# USBPD_CH211.net
KiCad netlist of a schematic drawn in Altium Designer
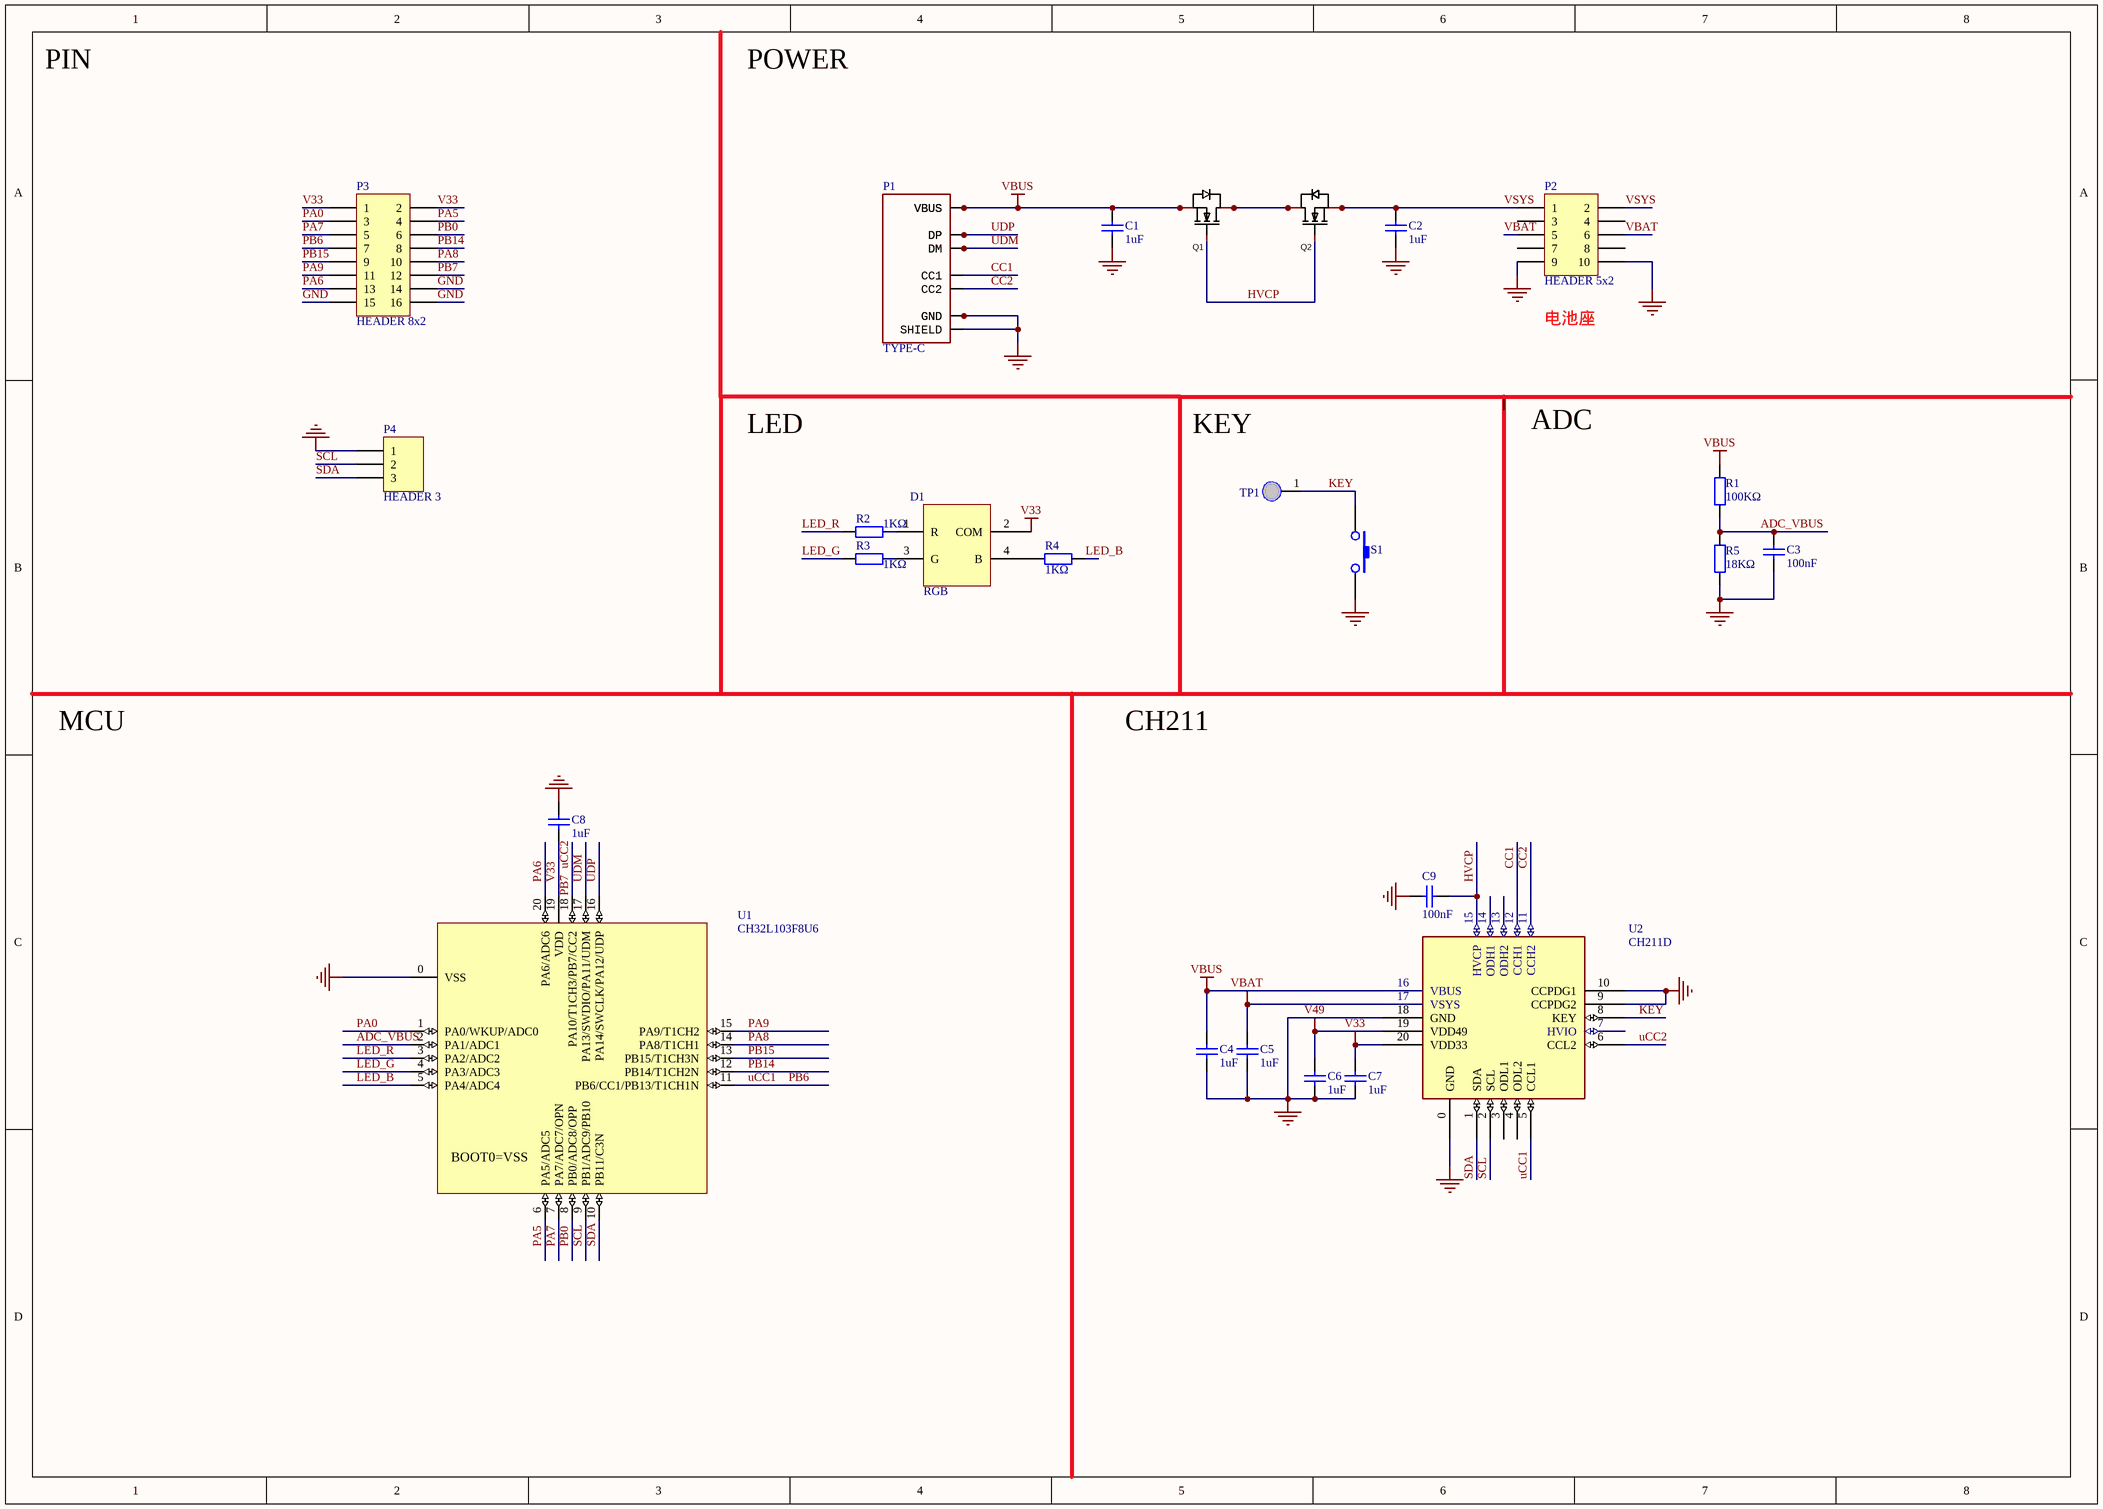
[diagram p0: USBPD_CH211.SchDoc]

(export (version "E")
  (design (tool "Eeschema 10.0.6"))
  (components
    (comp (ref "C1")
      (value "1uF")
      (footprint "0402_C")
      (description "贴片电容")
      (libsource (lib "Miscellaneous Devices LC") (part "0603 100nF (104) 10% 50V"))
    )
    (comp (ref "C2")
      (value "1uF")
      (footprint "0402_C")
      (description "贴片电容")
      (libsource (lib "Miscellaneous Devices LC") (part "0603 100nF (104) 10% 50V"))
    )
    (comp (ref "C3")
      (value "100nF")
      (footprint "0402_C")
      (description "贴片电容")
      (libsource (lib "Miscellaneous Devices LC") (part "0603 100nF (104) 10% 50V"))
    )
    (comp (ref "C4")
      (value "1uF")
      (footprint "0402_C")
      (description "贴片电容")
      (libsource (lib "Miscellaneous Devices LC") (part "0603 100nF (104) 10% 50V"))
    )
    (comp (ref "C5")
      (value "1uF")
      (footprint "0402_C")
      (description "贴片电容")
      (libsource (lib "Miscellaneous Devices LC") (part "0603 100nF (104) 10% 50V"))
    )
    (comp (ref "C6")
      (value "1uF")
      (footprint "0402_C")
      (description "贴片电容")
      (libsource (lib "Miscellaneous Devices LC") (part "0603 100nF (104) 10% 50V"))
    )
    (comp (ref "C7")
      (value "1uF")
      (footprint "0402_C")
      (description "贴片电容")
      (libsource (lib "Miscellaneous Devices LC") (part "0603 100nF (104) 10% 50V"))
    )
    (comp (ref "C8")
      (value "1uF")
      (footprint "0402_C")
      (description "贴片电容")
      (libsource (lib "Miscellaneous Devices LC") (part "0603 1uF (105) 10% 50V"))
    )
    (comp (ref "C9")
      (value "100nF")
      (footprint "0402_C")
      (description "贴片电容")
      (libsource (lib "Miscellaneous Devices LC") (part "0603 100nF (104) 10% 50V"))
    )
    (comp (ref "D1")
      (value "RGB")
      (footprint "RGB")
      (description "共阳")
      (libsource (lib "wch_sch_others") (part "RGB"))
    )
    (comp (ref "P1")
      (value "TYPE-C")
      (footprint "TYPE-C-Receptacle-2.0")
      (libsource (lib "Miscellaneous SCH Lib") (part "TYPE-C-Receptacle-RefDesign"))
    )
    (comp (ref "P2")
      (value "HEADER 5x2")
      (footprint "MYPCB:IDC10-2.54mm")
      (description "Header, 5-Pin, Dual row")
      (libsource (lib "wch_sch_others") (part "HEADER 5x2"))
    )
    (comp (ref "P3")
      (value "HEADER 8x2")
      (footprint "MYPCB:IDC16-2.54mm")
      (description "Header, 8-Pin, Dual row")
      (libsource (lib "wch_sch_others") (part "HEADER 8x2"))
    )
    (comp (ref "P4")
      (value "HEADER 3")
      (footprint "SIP3-2.54MM")
      (description "Header, 3-Pin")
      (libsource (lib "wch_sch_others") (part "HEADER 3"))
    )
    (comp (ref "Q1")
      (value "ASDM40N52E-R")
      (footprint "DFN-8_L3.1-W3.0-P0.65-LS3.3-BL")
      (description "DFN_NMOS")
      (fields (field (name "MANUFACTURER") "Ascend(安森德)"))
      (libsource (lib "Zcc") (part "NMOS_DFN3*3.1"))
    )
    (comp (ref "Q2")
      (value "ASDM40N52E-R")
      (footprint "DFN-8_L3.1-W3.0-P0.65-LS3.3-BL")
      (description "DFN_NMOS")
      (fields (field (name "MANUFACTURER") "Ascend(安森德)"))
      (libsource (lib "Zcc") (part "NMOS_DFN3*3.1"))
    )
    (comp (ref "R1")
      (value "100KΩ")
      (footprint "0402")
      (description "贴片电阻")
      (libsource (lib "Miscellaneous Devices LC") (part "0603 100KΩ (1003) 1%"))
    )
    (comp (ref "R2")
      (value "1KΩ")
      (footprint "0402")
      (description "贴片电阻")
      (libsource (lib "") (part "0603 100KΩ (1003) 1%_1"))
    )
    (comp (ref "R3")
      (value "1KΩ")
      (footprint "0402")
      (description "贴片电阻")
      (libsource (lib "") (part "0603 100KΩ (1003) 1%_1"))
    )
    (comp (ref "R4")
      (value "1KΩ")
      (footprint "0402")
      (description "贴片电阻")
      (libsource (lib "") (part "0603 100KΩ (1003) 1%_1"))
    )
    (comp (ref "R5")
      (value "18KΩ")
      (footprint "0402")
      (description "贴片电阻")
      (libsource (lib "Miscellaneous Devices LC") (part "0603 100KΩ (1003) 1%"))
    )
    (comp (ref "S1")
      (value "KEY")
      (footprint "SMD_6.1x3.65x2.5mm-KEY")
      (libsource (lib "wch_sch_others") (part "KEY1"))
    )
    (comp (ref "TP1")
      (value "Testpoint")
      (footprint "TESTPOINT3")
      (description "测试点")
      (libsource (lib "wch_sch_others") (part "Testpoint"))
    )
    (comp (ref "U1")
      (value "CH32L103F8U6")
      (footprint "QFN20_3X3")
      (description "RISC-V LMD-MCU, 96MHz, USB, Type-C/PD-5K1, CAN, OPA, lower power")
      (libsource (lib "DHXXXSCH111") (part "CH32L103F8U6"))
    )
    (comp (ref "U2")
      (value "CH211D")
      (footprint "QFN20_3X3")
      (description "28V USB PD & Type-C high voltage interface")
      (libsource (lib "CHXXX") (part "CH211D"))
    )
  )
  (nets
    (net (code "1") (name "/ADC_VBUS") (class "Default")
      (node (ref "C3") (pin "2") (pinfunction "2_2") (pintype "passive"))
      (node (ref "R1") (pin "2") (pinfunction "2_2") (pintype "passive"))
      (node (ref "R5") (pin "1") (pinfunction "1_1") (pintype "passive"))
      (node (ref "U1") (pin "2") (pinfunction "PA1/ADC1_2") (pintype "bidirectional"))
    )
    (net (code "2") (name "/CC1") (class "Default")
      (node (ref "P1") (pin "A5") (pinfunction "CC1_A5") (pintype "passive"))
      (node (ref "U2") (pin "12") (pinfunction "CCH1_12") (pintype "bidirectional"))
    )
    (net (code "3") (name "/CC2") (class "Default")
      (node (ref "P1") (pin "B5") (pinfunction "CC2_B5") (pintype "passive"))
      (node (ref "U2") (pin "11") (pinfunction "CCH2_11") (pintype "bidirectional"))
    )
    (net (code "4") (name "/HVCP") (class "Default")
      (node (ref "C9") (pin "1") (pinfunction "1_1") (pintype "passive"))
      (node (ref "Q1") (pin "4") (pinfunction "G_4") (pintype "passive"))
      (node (ref "Q2") (pin "4") (pinfunction "G_4") (pintype "passive"))
      (node (ref "U2") (pin "15") (pinfunction "HVCP_15") (pintype "bidirectional"))
    )
    (net (code "5") (name "/KEY") (class "Default")
      (node (ref "S1") (pin "1") (pinfunction "1_1") (pintype "passive"))
      (node (ref "TP1") (pin "1") (pintype "passive"))
      (node (ref "U2") (pin "8") (pinfunction "KEY_8") (pintype "bidirectional"))
    )
    (net (code "6") (name "/LED_B") (class "Default")
      (node (ref "R4") (pin "2") (pinfunction "2_2") (pintype "passive"))
      (node (ref "U1") (pin "5") (pinfunction "PA4/ADC4_5") (pintype "bidirectional"))
    )
    (net (code "7") (name "/LED_G") (class "Default")
      (node (ref "R3") (pin "1") (pinfunction "1_1") (pintype "passive"))
      (node (ref "U1") (pin "4") (pinfunction "PA3/ADC3_4") (pintype "bidirectional"))
    )
    (net (code "8") (name "/LED_R") (class "Default")
      (node (ref "R2") (pin "1") (pinfunction "1_1") (pintype "passive"))
      (node (ref "U1") (pin "3") (pinfunction "PA2/ADC2_3") (pintype "bidirectional"))
    )
    (net (code "9") (name "/PA0") (class "Default")
      (node (ref "P3") (pin "3") (pinfunction "3_3") (pintype "passive"))
      (node (ref "U1") (pin "1") (pinfunction "PA0/WKUP/ADC0_1") (pintype "bidirectional"))
    )
    (net (code "10") (name "/PA5") (class "Default")
      (node (ref "P3") (pin "4") (pinfunction "4_4") (pintype "passive"))
      (node (ref "U1") (pin "6") (pinfunction "PA5/ADC5_6") (pintype "bidirectional"))
    )
    (net (code "11") (name "/PA6") (class "Default")
      (node (ref "P3") (pin "13") (pinfunction "13_13") (pintype "passive"))
      (node (ref "U1") (pin "20") (pinfunction "PA6/ADC6_20") (pintype "bidirectional"))
    )
    (net (code "12") (name "/PA7") (class "Default")
      (node (ref "P3") (pin "5") (pinfunction "5_5") (pintype "passive"))
      (node (ref "U1") (pin "7") (pinfunction "PA7/ADC7/OPN_7") (pintype "bidirectional"))
    )
    (net (code "13") (name "/PA8") (class "Default")
      (node (ref "P3") (pin "10") (pinfunction "10_10") (pintype "passive"))
      (node (ref "U1") (pin "14") (pinfunction "PA8/T1CH1_14") (pintype "bidirectional"))
    )
    (net (code "14") (name "/PA9") (class "Default")
      (node (ref "P3") (pin "11") (pinfunction "11_11") (pintype "passive"))
      (node (ref "U1") (pin "15") (pinfunction "PA9/T1CH2_15") (pintype "bidirectional"))
    )
    (net (code "15") (name "/PB0") (class "Default")
      (node (ref "P3") (pin "6") (pinfunction "6_6") (pintype "passive"))
      (node (ref "U1") (pin "8") (pinfunction "PB0/ADC8/OPP_8") (pintype "bidirectional"))
    )
    (net (code "16") (name "/PB6") (class "Default")
      (node (ref "P3") (pin "7") (pinfunction "7_7") (pintype "passive"))
      (node (ref "U1") (pin "11") (pinfunction "PB6/CC1/PB13/T1CH1N_11") (pintype "bidirectional"))
      (node (ref "U2") (pin "5") (pinfunction "CCL1_5") (pintype "bidirectional"))
    )
    (net (code "17") (name "/PB7") (class "Default")
      (node (ref "P3") (pin "12") (pinfunction "12_12") (pintype "passive"))
      (node (ref "U1") (pin "18") (pinfunction "PA10/T1CH3/PB7/CC2_18") (pintype "bidirectional"))
      (node (ref "U2") (pin "6") (pinfunction "CCL2_6") (pintype "bidirectional"))
    )
    (net (code "18") (name "/PB14") (class "Default")
      (node (ref "P3") (pin "8") (pinfunction "8_8") (pintype "passive"))
      (node (ref "U1") (pin "12") (pinfunction "PB14/T1CH2N_12") (pintype "bidirectional"))
    )
    (net (code "19") (name "/PB15") (class "Default")
      (node (ref "P3") (pin "9") (pinfunction "9_9") (pintype "passive"))
      (node (ref "U1") (pin "13") (pinfunction "PB15/T1CH3N_13") (pintype "bidirectional"))
    )
    (net (code "20") (name "/SCL") (class "Default")
      (node (ref "P4") (pin "2") (pinfunction "2_2") (pintype "passive"))
      (node (ref "U1") (pin "9") (pinfunction "PB1/ADC9/PB10_9") (pintype "bidirectional"))
      (node (ref "U2") (pin "2") (pinfunction "SCL_2") (pintype "bidirectional"))
    )
    (net (code "21") (name "/SDA") (class "Default")
      (node (ref "P4") (pin "3") (pinfunction "3_3") (pintype "passive"))
      (node (ref "U1") (pin "10") (pinfunction "PB11/C3N_10") (pintype "bidirectional"))
      (node (ref "U2") (pin "1") (pinfunction "SDA_1") (pintype "bidirectional"))
    )
    (net (code "22") (name "/UDM") (class "Default")
      (node (ref "P1") (pin "A7") (pinfunction "DM_A7") (pintype "passive"))
      (node (ref "P1") (pin "B7") (pinfunction "DM_B7") (pintype "passive"))
      (node (ref "U1") (pin "17") (pinfunction "PA13/SWDIO/PA11/UDM_17") (pintype "bidirectional"))
    )
    (net (code "23") (name "/UDP") (class "Default")
      (node (ref "P1") (pin "A6") (pinfunction "DP_A6") (pintype "passive"))
      (node (ref "P1") (pin "B6") (pinfunction "DP_B6") (pintype "passive"))
      (node (ref "U1") (pin "16") (pinfunction "PA14/SWCLK/PA12/UDP_16") (pintype "bidirectional"))
    )
    (net (code "24") (name "/VSYS") (class "Default")
      (node (ref "C2") (pin "2") (pinfunction "2_2") (pintype "passive"))
      (node (ref "P2") (pin "1") (pinfunction "1_1") (pintype "passive"))
      (node (ref "P2") (pin "2") (pinfunction "2_2") (pintype "passive"))
      (node (ref "Q2") (pin "1") (pinfunction "S_1") (pintype "passive"))
      (node (ref "Q2") (pin "2") (pinfunction "S_2") (pintype "passive"))
      (node (ref "Q2") (pin "3") (pinfunction "S_3") (pintype "passive"))
    )
    (net (code "25") (name "GND") (class "Default")
      (node (ref "C1") (pin "1") (pinfunction "1_1") (pintype "passive"))
      (node (ref "C2") (pin "1") (pinfunction "1_1") (pintype "passive"))
      (node (ref "C3") (pin "1") (pinfunction "1_1") (pintype "passive"))
      (node (ref "C4") (pin "1") (pinfunction "1_1") (pintype "passive"))
      (node (ref "C5") (pin "1") (pinfunction "1_1") (pintype "passive"))
      (node (ref "C6") (pin "1") (pinfunction "1_1") (pintype "passive"))
      (node (ref "C7") (pin "1") (pinfunction "1_1") (pintype "passive"))
      (node (ref "C8") (pin "1") (pinfunction "1_1") (pintype "passive"))
      (node (ref "C9") (pin "2") (pinfunction "2_2") (pintype "passive"))
      (node (ref "P1") (pin "0") (pinfunction "SHIELD_0") (pintype "passive"))
      (node (ref "P1") (pin "A1") (pinfunction "GND_A1") (pintype "passive"))
      (node (ref "P1") (pin "A12") (pinfunction "GND_A12") (pintype "passive"))
      (node (ref "P1") (pin "B1") (pinfunction "GND_B1") (pintype "passive"))
      (node (ref "P1") (pin "B12") (pinfunction "GND_B12") (pintype "passive"))
      (node (ref "P2") (pin "10") (pinfunction "10_10") (pintype "passive"))
      (node (ref "P2") (pin "9") (pinfunction "9_9") (pintype "passive"))
      (node (ref "P3") (pin "14") (pinfunction "14_14") (pintype "passive"))
      (node (ref "P3") (pin "15") (pinfunction "15_15") (pintype "passive"))
      (node (ref "P3") (pin "16") (pinfunction "16_16") (pintype "passive"))
      (node (ref "P4") (pin "1") (pinfunction "1_1") (pintype "passive"))
      (node (ref "R5") (pin "2") (pinfunction "2_2") (pintype "passive"))
      (node (ref "S1") (pin "2") (pinfunction "2_2") (pintype "passive"))
      (node (ref "U1") (pin "0") (pinfunction "VSS_0") (pintype "power_in"))
      (node (ref "U2") (pin "0") (pinfunction "GND_0") (pintype "power_in"))
      (node (ref "U2") (pin "10") (pinfunction "CCPDG1_10") (pintype "power_in"))
      (node (ref "U2") (pin "18") (pinfunction "GND_18") (pintype "power_in"))
      (node (ref "U2") (pin "9") (pinfunction "CCPDG2_9") (pintype "power_in"))
    )
    (net (code "26") (name "Net-(D1-B)") (class "Default")
      (node (ref "D1") (pin "4") (pinfunction "B_4") (pintype "passive"))
      (node (ref "R4") (pin "1") (pinfunction "1_1") (pintype "passive"))
    )
    (net (code "27") (name "Net-(D1-G)") (class "Default")
      (node (ref "D1") (pin "3") (pinfunction "G_3") (pintype "passive"))
      (node (ref "R3") (pin "2") (pinfunction "2_2") (pintype "passive"))
    )
    (net (code "28") (name "Net-(D1-R)") (class "Default")
      (node (ref "D1") (pin "1") (pinfunction "R_1") (pintype "passive"))
      (node (ref "R2") (pin "2") (pinfunction "2_2") (pintype "passive"))
    )
    (net (code "29") (name "Net-(Q1-D-Pad5)") (class "Default")
      (node (ref "Q1") (pin "5") (pinfunction "D_5") (pintype "passive"))
      (node (ref "Q1") (pin "6") (pinfunction "D_6") (pintype "passive"))
      (node (ref "Q1") (pin "7") (pinfunction "D_7") (pintype "passive"))
      (node (ref "Q1") (pin "8") (pinfunction "D_8") (pintype "passive"))
      (node (ref "Q2") (pin "5") (pinfunction "D_5") (pintype "passive"))
      (node (ref "Q2") (pin "6") (pinfunction "D_6") (pintype "passive"))
      (node (ref "Q2") (pin "7") (pinfunction "D_7") (pintype "passive"))
      (node (ref "Q2") (pin "8") (pinfunction "D_8") (pintype "passive"))
    )
    (net (code "30") (name "V33") (class "Default")
      (node (ref "C7") (pin "2") (pinfunction "2_2") (pintype "passive"))
      (node (ref "C8") (pin "2") (pinfunction "2_2") (pintype "passive"))
      (node (ref "D1") (pin "2") (pinfunction "COM_2") (pintype "passive"))
      (node (ref "P3") (pin "1") (pinfunction "1_1") (pintype "passive"))
      (node (ref "P3") (pin "2") (pinfunction "2_2") (pintype "passive"))
      (node (ref "U1") (pin "19") (pinfunction "VDD_19") (pintype "power_in"))
      (node (ref "U2") (pin "20") (pinfunction "VDD33_20") (pintype "power_in"))
    )
    (net (code "31") (name "V49") (class "Default")
      (node (ref "C6") (pin "2") (pinfunction "2_2") (pintype "passive"))
      (node (ref "U2") (pin "19") (pinfunction "VDD49_19") (pintype "power_in"))
    )
    (net (code "32") (name "VBAT") (class "Default")
      (node (ref "C5") (pin "2") (pinfunction "2_2") (pintype "passive"))
      (node (ref "P2") (pin "5") (pinfunction "5_5") (pintype "passive"))
      (node (ref "P2") (pin "6") (pinfunction "6_6") (pintype "passive"))
      (node (ref "U2") (pin "17") (pinfunction "VSYS_17") (pintype "power_in"))
    )
    (net (code "33") (name "VBUS") (class "Default")
      (node (ref "C1") (pin "2") (pinfunction "2_2") (pintype "passive"))
      (node (ref "C4") (pin "2") (pinfunction "2_2") (pintype "passive"))
      (node (ref "P1") (pin "A4") (pinfunction "VBUS_A4") (pintype "passive"))
      (node (ref "P1") (pin "A9") (pinfunction "VBUS_A9") (pintype "passive"))
      (node (ref "P1") (pin "B4") (pinfunction "VBUS_B4") (pintype "passive"))
      (node (ref "P1") (pin "B9") (pinfunction "VBUS_B9") (pintype "passive"))
      (node (ref "Q1") (pin "1") (pinfunction "S_1") (pintype "passive"))
      (node (ref "Q1") (pin "2") (pinfunction "S_2") (pintype "passive"))
      (node (ref "Q1") (pin "3") (pinfunction "S_3") (pintype "passive"))
      (node (ref "R1") (pin "1") (pinfunction "1_1") (pintype "passive"))
      (node (ref "U2") (pin "16") (pinfunction "VBUS_16") (pintype "power_in"))
    )
    (net (code "34") (name "unconnected-(P2-Pad3)") (class "Default")
      (node (ref "P2") (pin "3") (pinfunction "3_3") (pintype "passive"))
    )
    (net (code "35") (name "unconnected-(P2-Pad4)") (class "Default")
      (node (ref "P2") (pin "4") (pinfunction "4_4") (pintype "passive"))
    )
    (net (code "36") (name "unconnected-(P2-Pad7)") (class "Default")
      (node (ref "P2") (pin "7") (pinfunction "7_7") (pintype "passive"))
    )
    (net (code "37") (name "unconnected-(P2-Pad8)") (class "Default")
      (node (ref "P2") (pin "8") (pinfunction "8_8") (pintype "passive"))
    )
    (net (code "38") (name "unconnected-(U2-HVIO-Pad7)") (class "Default")
      (node (ref "U2") (pin "7") (pinfunction "HVIO_7") (pintype "bidirectional"))
    )
    (net (code "39") (name "unconnected-(U2-ODH1-Pad14)") (class "Default")
      (node (ref "U2") (pin "14") (pinfunction "ODH1_14") (pintype "bidirectional"))
    )
    (net (code "40") (name "unconnected-(U2-ODH2-Pad13)") (class "Default")
      (node (ref "U2") (pin "13") (pinfunction "ODH2_13") (pintype "bidirectional"))
    )
    (net (code "41") (name "unconnected-(U2-ODL1-Pad3)") (class "Default")
      (node (ref "U2") (pin "3") (pinfunction "ODL1_3") (pintype "bidirectional"))
    )
    (net (code "42") (name "unconnected-(U2-ODL2-Pad4)") (class "Default")
      (node (ref "U2") (pin "4") (pinfunction "ODL2_4") (pintype "bidirectional"))
    )
  )
)
